# Buhatron.net
KiCad netlist of a schematic drawn in EAGLE
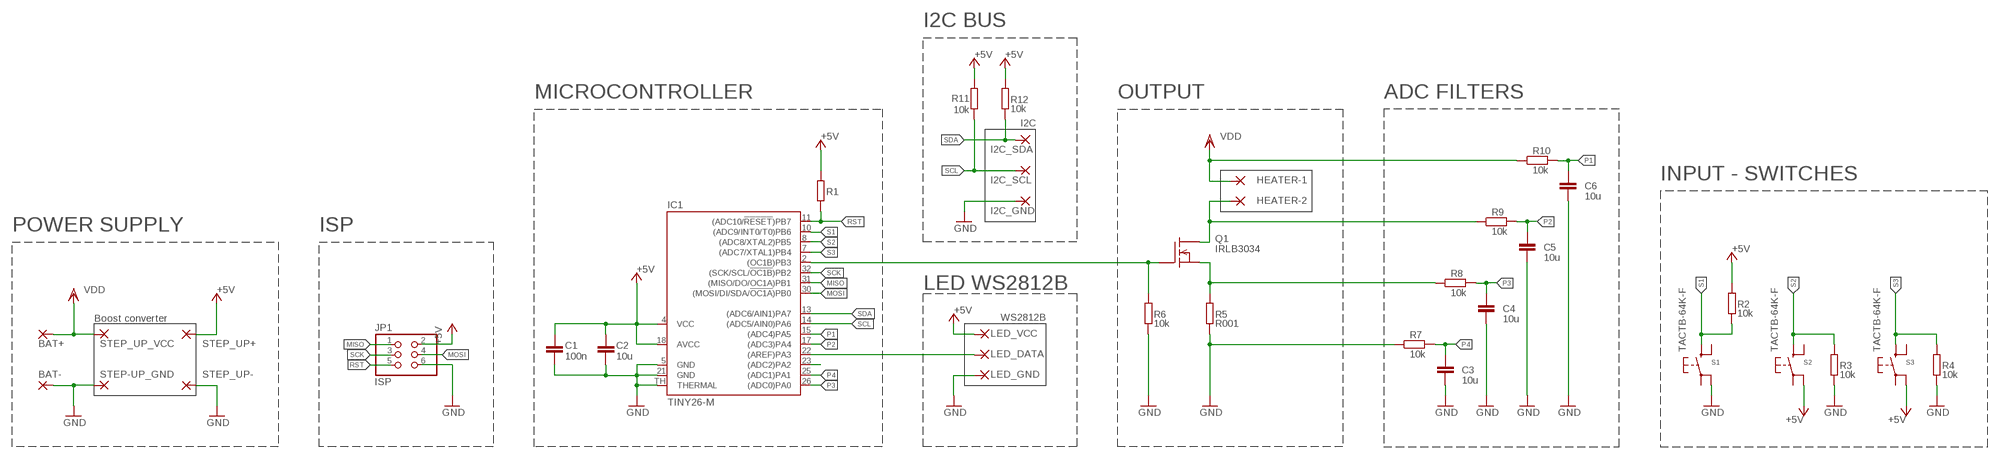
[diagram p0: schematic, sheet 1]

(export (version "E")
  (design (tool "Eeschema 10.0.6"))
  (components
    (comp (ref "BAT+")
      (value "3,81/1,4")
      (footprint "eagle-import:3,81_1,4")
      (libsource (lib "eagle-import") (part "3,81/1,4"))
    )
    (comp (ref "BAT-")
      (value "3,81/1,4")
      (footprint "eagle-import:3,81_1,4")
      (libsource (lib "eagle-import") (part "3,81/1,4"))
    )
    (comp (ref "C1")
      (value "100n")
      (footprint "eagle-import:C0805")
      (libsource (lib "eagle-import") (part "C-EUC0805"))
    )
    (comp (ref "C2")
      (value "10u")
      (footprint "eagle-import:C0805")
      (libsource (lib "eagle-import") (part "C-EUC0805"))
    )
    (comp (ref "C3")
      (value "10u")
      (footprint "eagle-import:C0805")
      (libsource (lib "eagle-import") (part "C-EUC0805"))
    )
    (comp (ref "C4")
      (value "10u")
      (footprint "eagle-import:C0805")
      (libsource (lib "eagle-import") (part "C-EUC0805"))
    )
    (comp (ref "C5")
      (value "10u")
      (footprint "eagle-import:C0805")
      (libsource (lib "eagle-import") (part "C-EUC0805"))
    )
    (comp (ref "C6")
      (value "10u")
      (footprint "eagle-import:C0805")
      (libsource (lib "eagle-import") (part "C-EUC0805"))
    )
    (comp (ref "HEATER-1")
      (value "3,81/1,4")
      (footprint "eagle-import:3,81_1,4")
      (libsource (lib "eagle-import") (part "3,81/1,4"))
    )
    (comp (ref "HEATER-2")
      (value "3,81/1,4")
      (footprint "eagle-import:3,81_1,4")
      (libsource (lib "eagle-import") (part "3,81/1,4"))
    )
    (comp (ref "I2C_GND")
      (value "SMD2")
      (footprint "eagle-import:SMD1,27-2,54")
      (libsource (lib "eagle-import") (part "SMD2"))
    )
    (comp (ref "I2C_SCL")
      (value "SMD2")
      (footprint "eagle-import:SMD1,27-2,54")
      (libsource (lib "eagle-import") (part "SMD2"))
    )
    (comp (ref "I2C_SDA")
      (value "SMD2")
      (footprint "eagle-import:SMD1,27-2,54")
      (libsource (lib "eagle-import") (part "SMD2"))
    )
    (comp (ref "IC1")
      (value "TINY26-M")
      (footprint "eagle-import:MLF32-TH")
      (libsource (lib "eagle-import") (part "TINY26-M"))
    )
    (comp (ref "JP1")
      (value "ISP")
      (footprint "eagle-import:2X03")
      (fields (field (name "SPICEPREFIX") "X"))
      (libsource (lib "eagle-import") (part "PINHD-2X3"))
    )
    (comp (ref "LED_DATA")
      (value "SMD2")
      (footprint "eagle-import:SMD1,27-2,54")
      (libsource (lib "eagle-import") (part "SMD2"))
    )
    (comp (ref "LED_GND")
      (value "SMD2")
      (footprint "eagle-import:SMD1,27-2,54")
      (libsource (lib "eagle-import") (part "SMD2"))
    )
    (comp (ref "LED_VCC")
      (value "SMD2")
      (footprint "eagle-import:SMD1,27-2,54")
      (libsource (lib "eagle-import") (part "SMD2"))
    )
    (comp (ref "Q1")
      (value "IRLB3034")
      (footprint "eagle-import:TO220")
      (libsource (lib "eagle-import") (part "BUZ11"))
    )
    (comp (ref "R1")
      (value "R-EU_M0805")
      (footprint "eagle-import:M0805")
      (libsource (lib "eagle-import") (part "R-EU_M0805"))
    )
    (comp (ref "R2")
      (value "10k")
      (footprint "eagle-import:M0805")
      (libsource (lib "eagle-import") (part "R-EU_M0805"))
    )
    (comp (ref "R3")
      (value "10k")
      (footprint "eagle-import:M0805")
      (libsource (lib "eagle-import") (part "R-EU_M0805"))
    )
    (comp (ref "R4")
      (value "10k")
      (footprint "eagle-import:M0805")
      (libsource (lib "eagle-import") (part "R-EU_M0805"))
    )
    (comp (ref "R5")
      (value "R001")
      (footprint "eagle-import:R2512")
      (libsource (lib "eagle-import") (part "R-EU_R2512"))
    )
    (comp (ref "R6")
      (value "10k")
      (footprint "eagle-import:M0805")
      (libsource (lib "eagle-import") (part "R-EU_M0805"))
    )
    (comp (ref "R7")
      (value "10k")
      (footprint "eagle-import:M0805")
      (libsource (lib "eagle-import") (part "R-EU_M0805"))
    )
    (comp (ref "R8")
      (value "10k")
      (footprint "eagle-import:M0805")
      (libsource (lib "eagle-import") (part "R-EU_M0805"))
    )
    (comp (ref "R9")
      (value "10k")
      (footprint "eagle-import:M0805")
      (libsource (lib "eagle-import") (part "R-EU_M0805"))
    )
    (comp (ref "R10")
      (value "10k")
      (footprint "eagle-import:M0805")
      (libsource (lib "eagle-import") (part "R-EU_M0805"))
    )
    (comp (ref "R11")
      (value "10k")
      (footprint "eagle-import:M0805")
      (libsource (lib "eagle-import") (part "R-EU_M0805"))
    )
    (comp (ref "R12")
      (value "10k")
      (footprint "eagle-import:M0805")
      (libsource (lib "eagle-import") (part "R-EU_M0805"))
    )
    (comp (ref "S1")
      (value "TACTB-64K-F")
      (footprint "eagle-import:8-4.8_SMD")
      (libsource (lib "eagle-import") (part "TACTB-64K-F"))
    )
    (comp (ref "S2")
      (value "TACTB-64K-F")
      (footprint "eagle-import:8-4.8_SMD")
      (libsource (lib "eagle-import") (part "TACTB-64K-F"))
    )
    (comp (ref "S3")
      (value "TACTB-64K-F")
      (footprint "eagle-import:8-4.8_SMD")
      (libsource (lib "eagle-import") (part "TACTB-64K-F"))
    )
    (comp (ref "STEP-UP_GND")
      (value "3,81/1,4")
      (footprint "eagle-import:3,81_1,4")
      (libsource (lib "eagle-import") (part "3,81/1,4"))
    )
    (comp (ref "STEP_UP+")
      (value "3,81/1,4")
      (footprint "eagle-import:3,81_1,4")
      (libsource (lib "eagle-import") (part "3,81/1,4"))
    )
    (comp (ref "STEP_UP-")
      (value "3,81/1,4")
      (footprint "eagle-import:3,81_1,4")
      (libsource (lib "eagle-import") (part "3,81/1,4"))
    )
    (comp (ref "STEP_UP_VCC")
      (value "3,81/1,4")
      (footprint "eagle-import:3,81_1,4")
      (libsource (lib "eagle-import") (part "3,81/1,4"))
    )
  )
  (nets
    (net (code "1") (name "+5V") (class "Default")
      (node (ref "C1") (pin "1") (pinfunction "1_1") (pintype "passive"))
      (node (ref "C2") (pin "1") (pinfunction "1_1") (pintype "passive"))
      (node (ref "IC1") (pin "18") (pinfunction "AVCC_18") (pintype "power_in"))
      (node (ref "IC1") (pin "4") (pinfunction "VCC_4") (pintype "power_in"))
      (node (ref "JP1") (pin "2") (pinfunction "2_2") (pintype "passive"))
      (node (ref "LED_VCC") (pin "1") (pinfunction "P_1") (pintype "passive"))
      (node (ref "R1") (pin "2") (pinfunction "2_2") (pintype "passive"))
      (node (ref "R11") (pin "2") (pinfunction "2_2") (pintype "passive"))
      (node (ref "R12") (pin "2") (pinfunction "2_2") (pintype "passive"))
      (node (ref "R2") (pin "2") (pinfunction "2_2") (pintype "passive"))
      (node (ref "S2") (pin "P$4") (pinfunction "G$4_P$4") (pintype "passive"))
      (node (ref "S3") (pin "P$4") (pinfunction "G$4_P$4") (pintype "passive"))
      (node (ref "STEP_UP+") (pin "1") (pinfunction "P_1") (pintype "passive"))
    )
    (net (code "2") (name "GND") (class "Default")
      (node (ref "BAT-") (pin "1") (pinfunction "P_1") (pintype "passive"))
      (node (ref "C1") (pin "2") (pinfunction "2_2") (pintype "passive"))
      (node (ref "C2") (pin "2") (pinfunction "2_2") (pintype "passive"))
      (node (ref "C3") (pin "2") (pinfunction "2_2") (pintype "passive"))
      (node (ref "C4") (pin "2") (pinfunction "2_2") (pintype "passive"))
      (node (ref "C5") (pin "2") (pinfunction "2_2") (pintype "passive"))
      (node (ref "C6") (pin "2") (pinfunction "2_2") (pintype "passive"))
      (node (ref "I2C_GND") (pin "1") (pinfunction "P_1") (pintype "passive"))
      (node (ref "IC1") (pin "21") (pinfunction "GND_21") (pintype "power_in"))
      (node (ref "IC1") (pin "5") (pinfunction "GND_5") (pintype "power_in"))
      (node (ref "IC1") (pin "TH") (pinfunction "THERMAL_TH") (pintype "input"))
      (node (ref "JP1") (pin "6") (pinfunction "6_6") (pintype "passive"))
      (node (ref "LED_GND") (pin "1") (pinfunction "P_1") (pintype "passive"))
      (node (ref "R3") (pin "1") (pinfunction "1_1") (pintype "passive"))
      (node (ref "R4") (pin "1") (pinfunction "1_1") (pintype "passive"))
      (node (ref "R5") (pin "1") (pinfunction "1_1") (pintype "passive"))
      (node (ref "R6") (pin "1") (pinfunction "1_1") (pintype "passive"))
      (node (ref "R7") (pin "1") (pinfunction "1_1") (pintype "passive"))
      (node (ref "S1") (pin "P$4") (pinfunction "G$4_P$4") (pintype "passive"))
      (node (ref "STEP-UP_GND") (pin "1") (pinfunction "P_1") (pintype "passive"))
      (node (ref "STEP_UP-") (pin "1") (pinfunction "P_1") (pintype "passive"))
    )
    (net (code "3") (name "MISO") (class "Default")
      (node (ref "IC1") (pin "31") (pinfunction "(MISO/DO/OC1A)PB1_31") (pintype "bidirectional"))
      (node (ref "JP1") (pin "1") (pinfunction "1_1") (pintype "passive"))
    )
    (net (code "4") (name "MOSI") (class "Default")
      (node (ref "IC1") (pin "30") (pinfunction "(MOSI/DI/SDA/~{OC1A})PB0_30") (pintype "bidirectional"))
      (node (ref "JP1") (pin "4") (pinfunction "4_4") (pintype "passive"))
    )
    (net (code "5") (name "Net-(HEATER-2-P)") (class "Default")
      (node (ref "HEATER-2") (pin "1") (pinfunction "P_1") (pintype "passive"))
      (node (ref "Q1") (pin "2") (pinfunction "D_2") (pintype "passive"))
      (node (ref "R9") (pin "1") (pinfunction "1_1") (pintype "passive"))
    )
    (net (code "6") (name "Net-(IC1-(AREF)PA3)") (class "Default")
      (node (ref "IC1") (pin "22") (pinfunction "(AREF)PA3_22") (pintype "bidirectional"))
      (node (ref "LED_DATA") (pin "1") (pinfunction "P_1") (pintype "passive"))
    )
    (net (code "7") (name "Net-(IC1-(OC1B)PB3)") (class "Default")
      (node (ref "IC1") (pin "2") (pinfunction "(OC1B)PB3_2") (pintype "bidirectional"))
      (node (ref "Q1") (pin "1") (pinfunction "G_1") (pintype "passive"))
      (node (ref "R6") (pin "2") (pinfunction "2_2") (pintype "passive"))
    )
    (net (code "8") (name "Net-(Q1-S)") (class "Default")
      (node (ref "Q1") (pin "3") (pinfunction "S_3") (pintype "passive"))
      (node (ref "R5") (pin "2") (pinfunction "2_2") (pintype "passive"))
      (node (ref "R8") (pin "1") (pinfunction "1_1") (pintype "passive"))
    )
    (net (code "9") (name "P1") (class "Default")
      (node (ref "C6") (pin "1") (pinfunction "1_1") (pintype "passive"))
      (node (ref "IC1") (pin "15") (pinfunction "(ADC4)PA5_15") (pintype "bidirectional"))
      (node (ref "R10") (pin "2") (pinfunction "2_2") (pintype "passive"))
    )
    (net (code "10") (name "P2") (class "Default")
      (node (ref "C5") (pin "1") (pinfunction "1_1") (pintype "passive"))
      (node (ref "IC1") (pin "17") (pinfunction "(ADC3)PA4_17") (pintype "bidirectional"))
      (node (ref "R9") (pin "2") (pinfunction "2_2") (pintype "passive"))
    )
    (net (code "11") (name "P3") (class "Default")
      (node (ref "C4") (pin "1") (pinfunction "1_1") (pintype "passive"))
      (node (ref "IC1") (pin "26") (pinfunction "(ADC0)PA0_26") (pintype "bidirectional"))
      (node (ref "R8") (pin "2") (pinfunction "2_2") (pintype "passive"))
    )
    (net (code "12") (name "P4") (class "Default")
      (node (ref "C3") (pin "1") (pinfunction "1_1") (pintype "passive"))
      (node (ref "IC1") (pin "25") (pinfunction "(ADC1)PA1_25") (pintype "bidirectional"))
      (node (ref "R7") (pin "2") (pinfunction "2_2") (pintype "passive"))
    )
    (net (code "13") (name "RST") (class "Default")
      (node (ref "IC1") (pin "11") (pinfunction "(ADC10/~{RESET})PB7_11") (pintype "bidirectional"))
      (node (ref "JP1") (pin "5") (pinfunction "5_5") (pintype "passive"))
      (node (ref "R1") (pin "1") (pinfunction "1_1") (pintype "passive"))
    )
    (net (code "14") (name "S1") (class "Default")
      (node (ref "IC1") (pin "10") (pinfunction "(ADC9/INT0/T0)PB6_10") (pintype "bidirectional"))
      (node (ref "R2") (pin "1") (pinfunction "1_1") (pintype "passive"))
      (node (ref "S1") (pin "P$1") (pinfunction "G$1_P$1") (pintype "passive"))
    )
    (net (code "15") (name "S2") (class "Default")
      (node (ref "IC1") (pin "8") (pinfunction "(ADC8/XTAL2)PB5_8") (pintype "bidirectional"))
      (node (ref "R3") (pin "2") (pinfunction "2_2") (pintype "passive"))
      (node (ref "S2") (pin "P$1") (pinfunction "G$1_P$1") (pintype "passive"))
    )
    (net (code "16") (name "S3") (class "Default")
      (node (ref "IC1") (pin "7") (pinfunction "(ADC7/XTAL1)PB4_7") (pintype "bidirectional"))
      (node (ref "R4") (pin "2") (pinfunction "2_2") (pintype "passive"))
      (node (ref "S3") (pin "P$1") (pinfunction "G$1_P$1") (pintype "passive"))
    )
    (net (code "17") (name "SCK") (class "Default")
      (node (ref "IC1") (pin "32") (pinfunction "(SCK/SCL/~{OC1B})PB2_32") (pintype "bidirectional"))
      (node (ref "JP1") (pin "3") (pinfunction "3_3") (pintype "passive"))
    )
    (net (code "18") (name "SCL") (class "Default")
      (node (ref "I2C_SCL") (pin "1") (pinfunction "P_1") (pintype "passive"))
      (node (ref "IC1") (pin "14") (pinfunction "(ADC5/AIN0)PA6_14") (pintype "bidirectional"))
      (node (ref "R11") (pin "1") (pinfunction "1_1") (pintype "passive"))
    )
    (net (code "19") (name "SDA") (class "Default")
      (node (ref "I2C_SDA") (pin "1") (pinfunction "P_1") (pintype "passive"))
      (node (ref "IC1") (pin "13") (pinfunction "(ADC6/AIN1)PA7_13") (pintype "bidirectional"))
      (node (ref "R12") (pin "1") (pinfunction "1_1") (pintype "passive"))
    )
    (net (code "20") (name "VDD") (class "Default")
      (node (ref "BAT+") (pin "1") (pinfunction "P_1") (pintype "passive"))
      (node (ref "HEATER-1") (pin "1") (pinfunction "P_1") (pintype "passive"))
      (node (ref "R10") (pin "1") (pinfunction "1_1") (pintype "passive"))
      (node (ref "STEP_UP_VCC") (pin "1") (pinfunction "P_1") (pintype "passive"))
    )
    (net (code "21") (name "unconnected-(IC1-(ADC2)PA2-Pad23)") (class "Default")
      (node (ref "IC1") (pin "23") (pinfunction "(ADC2)PA2_23") (pintype "bidirectional"))
    )
    (net (code "22") (name "unconnected-(S1-G$2-PadP$2)") (class "Default")
      (node (ref "S1") (pin "P$2") (pinfunction "G$2_P$2") (pintype "passive"))
    )
    (net (code "23") (name "unconnected-(S1-G$3-PadP$3)") (class "Default")
      (node (ref "S1") (pin "P$3") (pinfunction "G$3_P$3") (pintype "passive"))
    )
    (net (code "24") (name "unconnected-(S2-G$2-PadP$2)") (class "Default")
      (node (ref "S2") (pin "P$2") (pinfunction "G$2_P$2") (pintype "passive"))
    )
    (net (code "25") (name "unconnected-(S2-G$3-PadP$3)") (class "Default")
      (node (ref "S2") (pin "P$3") (pinfunction "G$3_P$3") (pintype "passive"))
    )
    (net (code "26") (name "unconnected-(S3-G$2-PadP$2)") (class "Default")
      (node (ref "S3") (pin "P$2") (pinfunction "G$2_P$2") (pintype "passive"))
    )
    (net (code "27") (name "unconnected-(S3-G$3-PadP$3)") (class "Default")
      (node (ref "S3") (pin "P$3") (pinfunction "G$3_P$3") (pintype "passive"))
    )
  )
)
